# KW_Control.net
KiCad netlist of a schematic drawn in EAGLE
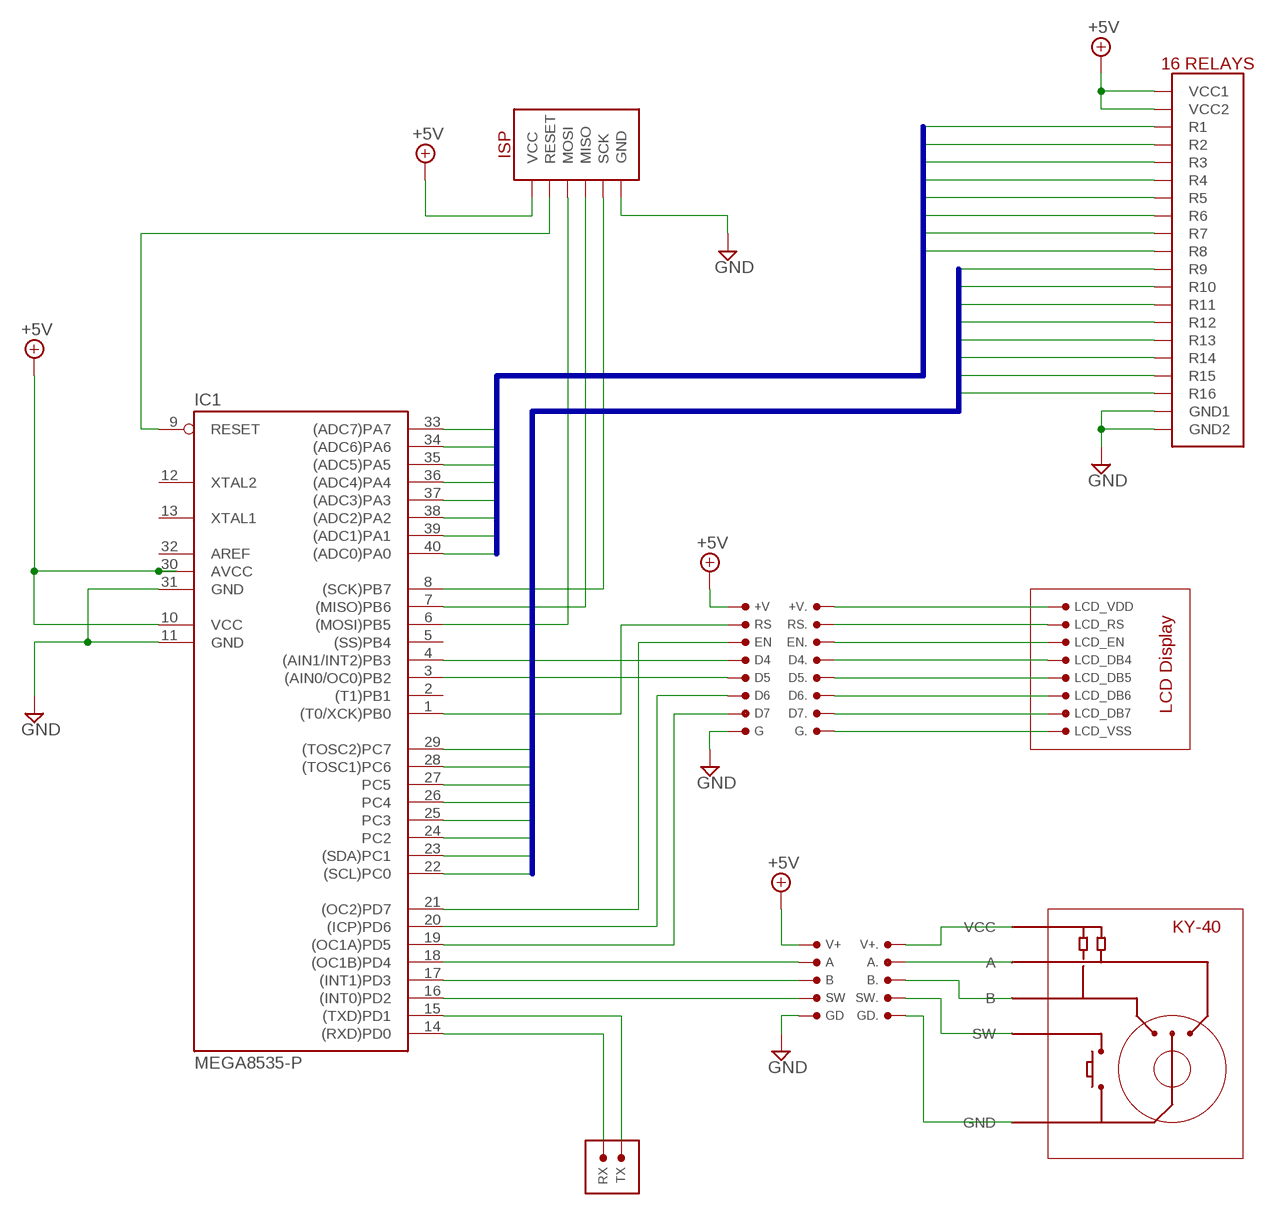
[diagram p0: schematic, sheet 1]

(export (version "E")
  (design (tool "Eeschema 10.0.6"))
  (components
    (comp (ref "+V")
      (value "PIN")
      (footprint "eagle-import:PIN")
      (libsource (lib "eagle-import") (part "PIN"))
    )
    (comp (ref "+V.")
      (value "PIN")
      (footprint "eagle-import:PIN")
      (libsource (lib "eagle-import") (part "PIN"))
    )
    (comp (ref "A")
      (value "PIN")
      (footprint "eagle-import:PIN")
      (libsource (lib "eagle-import") (part "PIN"))
    )
    (comp (ref "A.")
      (value "PIN")
      (footprint "eagle-import:PIN")
      (libsource (lib "eagle-import") (part "PIN"))
    )
    (comp (ref "B")
      (value "PIN")
      (footprint "eagle-import:PIN")
      (libsource (lib "eagle-import") (part "PIN"))
    )
    (comp (ref "B.")
      (value "PIN")
      (footprint "eagle-import:PIN")
      (libsource (lib "eagle-import") (part "PIN"))
    )
    (comp (ref "D4")
      (value "PIN")
      (footprint "eagle-import:PIN")
      (libsource (lib "eagle-import") (part "PIN"))
    )
    (comp (ref "D4.")
      (value "PIN")
      (footprint "eagle-import:PIN")
      (libsource (lib "eagle-import") (part "PIN"))
    )
    (comp (ref "D5")
      (value "PIN")
      (footprint "eagle-import:PIN")
      (libsource (lib "eagle-import") (part "PIN"))
    )
    (comp (ref "D5.")
      (value "PIN")
      (footprint "eagle-import:PIN")
      (libsource (lib "eagle-import") (part "PIN"))
    )
    (comp (ref "D6")
      (value "PIN")
      (footprint "eagle-import:PIN")
      (libsource (lib "eagle-import") (part "PIN"))
    )
    (comp (ref "D6.")
      (value "PIN")
      (footprint "eagle-import:PIN")
      (libsource (lib "eagle-import") (part "PIN"))
    )
    (comp (ref "D7")
      (value "PIN")
      (footprint "eagle-import:PIN")
      (libsource (lib "eagle-import") (part "PIN"))
    )
    (comp (ref "D7.")
      (value "PIN")
      (footprint "eagle-import:PIN")
      (libsource (lib "eagle-import") (part "PIN"))
    )
    (comp (ref "EN")
      (value "PIN")
      (footprint "eagle-import:PIN")
      (libsource (lib "eagle-import") (part "PIN"))
    )
    (comp (ref "EN.")
      (value "PIN")
      (footprint "eagle-import:PIN")
      (libsource (lib "eagle-import") (part "PIN"))
    )
    (comp (ref "G")
      (value "PIN")
      (footprint "eagle-import:PIN")
      (libsource (lib "eagle-import") (part "PIN"))
    )
    (comp (ref "G.")
      (value "PIN")
      (footprint "eagle-import:PIN")
      (libsource (lib "eagle-import") (part "PIN"))
    )
    (comp (ref "GD")
      (value "PIN")
      (footprint "eagle-import:PIN")
      (libsource (lib "eagle-import") (part "PIN"))
    )
    (comp (ref "GD.")
      (value "PIN")
      (footprint "eagle-import:PIN")
      (libsource (lib "eagle-import") (part "PIN"))
    )
    (comp (ref "IC1")
      (value "MEGA8535-P")
      (footprint "eagle-import:DIL40")
      (fields (field (name "MPN") "ATMEGA8535-16PU"))
      (libsource (lib "eagle-import") (part "MEGA8535-P"))
    )
    (comp (ref "IC2")
      (value "KY-40")
      (footprint "eagle-import:KY-40")
      (libsource (lib "eagle-import") (part "KY-40"))
    )
    (comp (ref "LCD_DB4")
      (value "PIN")
      (footprint "eagle-import:PIN")
      (libsource (lib "eagle-import") (part "PIN"))
    )
    (comp (ref "LCD_DB5")
      (value "PIN")
      (footprint "eagle-import:PIN")
      (libsource (lib "eagle-import") (part "PIN"))
    )
    (comp (ref "LCD_DB6")
      (value "PIN")
      (footprint "eagle-import:PIN")
      (libsource (lib "eagle-import") (part "PIN"))
    )
    (comp (ref "LCD_DB7")
      (value "PIN")
      (footprint "eagle-import:PIN")
      (libsource (lib "eagle-import") (part "PIN"))
    )
    (comp (ref "LCD_EN")
      (value "PIN")
      (footprint "eagle-import:PIN")
      (libsource (lib "eagle-import") (part "PIN"))
    )
    (comp (ref "LCD_RS")
      (value "PIN")
      (footprint "eagle-import:PIN")
      (libsource (lib "eagle-import") (part "PIN"))
    )
    (comp (ref "LCD_VDD")
      (value "PIN")
      (footprint "eagle-import:PIN")
      (libsource (lib "eagle-import") (part "PIN"))
    )
    (comp (ref "LCD_VSS")
      (value "PIN")
      (footprint "eagle-import:PIN")
      (libsource (lib "eagle-import") (part "PIN"))
    )
    (comp (ref "RS")
      (value "PIN")
      (footprint "eagle-import:PIN")
      (libsource (lib "eagle-import") (part "PIN"))
    )
    (comp (ref "RS.")
      (value "PIN")
      (footprint "eagle-import:PIN")
      (libsource (lib "eagle-import") (part "PIN"))
    )
    (comp (ref "RX")
      (value "PIN")
      (footprint "eagle-import:PIN")
      (libsource (lib "eagle-import") (part "PIN"))
    )
    (comp (ref "SW")
      (value "PIN")
      (footprint "eagle-import:PIN")
      (libsource (lib "eagle-import") (part "PIN"))
    )
    (comp (ref "SW.")
      (value "PIN")
      (footprint "eagle-import:PIN")
      (libsource (lib "eagle-import") (part "PIN"))
    )
    (comp (ref "TX")
      (value "PIN")
      (footprint "eagle-import:PIN")
      (libsource (lib "eagle-import") (part "PIN"))
    )
    (comp (ref "U$1")
      (value "ISP")
      (footprint "eagle-import:ISP")
      (libsource (lib "eagle-import") (part "ISP"))
    )
    (comp (ref "U$2")
      (value "RELAYS-16")
      (footprint "eagle-import:RELAYS-16")
      (libsource (lib "eagle-import") (part "RELAYS-16"))
    )
    (comp (ref "V+")
      (value "PIN")
      (footprint "eagle-import:PIN")
      (libsource (lib "eagle-import") (part "PIN"))
    )
    (comp (ref "V+.")
      (value "PIN")
      (footprint "eagle-import:PIN")
      (libsource (lib "eagle-import") (part "PIN"))
    )
  )
  (nets
    (net (code "1") (name "+5V") (class "Default")
      (node (ref "+V") (pin "P$1") (pinfunction "PIN1_P$1") (pintype "bidirectional"))
      (node (ref "IC1") (pin "10") (pinfunction "VCC_10") (pintype "power_in"))
      (node (ref "IC1") (pin "30") (pinfunction "AVCC_30") (pintype "power_in"))
      (node (ref "U$1") (pin "VCC") (pinfunction "VCC_VCC") (pintype "power_in"))
      (node (ref "U$2") (pin "VCC1") (pinfunction "VCC1_VCC1") (pintype "power_in"))
      (node (ref "U$2") (pin "VCC2") (pinfunction "VCC2_VCC2") (pintype "power_in"))
      (node (ref "V+") (pin "P$1") (pinfunction "PIN1_P$1") (pintype "bidirectional"))
    )
    (net (code "2") (name "/A1") (class "Default")
      (node (ref "IC1") (pin "40") (pinfunction "(ADC0)PA0_40") (pintype "bidirectional"))
      (node (ref "U$2") (pin "1") (pinfunction "R1_1") (pintype "input"))
    )
    (net (code "3") (name "/A2") (class "Default")
      (node (ref "IC1") (pin "39") (pinfunction "(ADC1)PA1_39") (pintype "bidirectional"))
      (node (ref "U$2") (pin "2") (pinfunction "R2_2") (pintype "input"))
    )
    (net (code "4") (name "/A3") (class "Default")
      (node (ref "IC1") (pin "38") (pinfunction "(ADC2)PA2_38") (pintype "bidirectional"))
      (node (ref "U$2") (pin "3") (pinfunction "R3_3") (pintype "input"))
    )
    (net (code "5") (name "/A4") (class "Default")
      (node (ref "IC1") (pin "37") (pinfunction "(ADC3)PA3_37") (pintype "bidirectional"))
      (node (ref "U$2") (pin "4") (pinfunction "R4_4") (pintype "input"))
    )
    (net (code "6") (name "/A5") (class "Default")
      (node (ref "IC1") (pin "36") (pinfunction "(ADC4)PA4_36") (pintype "bidirectional"))
      (node (ref "U$2") (pin "5") (pinfunction "R5_5") (pintype "input"))
    )
    (net (code "7") (name "/A6") (class "Default")
      (node (ref "IC1") (pin "35") (pinfunction "(ADC5)PA5_35") (pintype "bidirectional"))
      (node (ref "U$2") (pin "6") (pinfunction "R6_6") (pintype "input"))
    )
    (net (code "8") (name "/A7") (class "Default")
      (node (ref "IC1") (pin "34") (pinfunction "(ADC6)PA6_34") (pintype "bidirectional"))
      (node (ref "U$2") (pin "7") (pinfunction "R7_7") (pintype "input"))
    )
    (net (code "9") (name "/A8") (class "Default")
      (node (ref "IC1") (pin "33") (pinfunction "(ADC7)PA7_33") (pintype "bidirectional"))
      (node (ref "U$2") (pin "8") (pinfunction "R8_8") (pintype "input"))
    )
    (net (code "10") (name "/B1") (class "Default")
      (node (ref "IC1") (pin "22") (pinfunction "(SCL)PC0_22") (pintype "bidirectional"))
      (node (ref "U$2") (pin "9") (pinfunction "R9_9") (pintype "input"))
    )
    (net (code "11") (name "/B2") (class "Default")
      (node (ref "IC1") (pin "23") (pinfunction "(SDA)PC1_23") (pintype "bidirectional"))
      (node (ref "U$2") (pin "10") (pinfunction "R10_10") (pintype "input"))
    )
    (net (code "12") (name "/B3") (class "Default")
      (node (ref "IC1") (pin "24") (pinfunction "PC2_24") (pintype "bidirectional"))
      (node (ref "U$2") (pin "11") (pinfunction "R11_11") (pintype "input"))
    )
    (net (code "13") (name "/B4") (class "Default")
      (node (ref "IC1") (pin "25") (pinfunction "PC3_25") (pintype "bidirectional"))
      (node (ref "U$2") (pin "12") (pinfunction "R12_12") (pintype "input"))
    )
    (net (code "14") (name "/B5") (class "Default")
      (node (ref "IC1") (pin "26") (pinfunction "PC4_26") (pintype "bidirectional"))
      (node (ref "U$2") (pin "13") (pinfunction "R13_13") (pintype "input"))
    )
    (net (code "15") (name "/B6") (class "Default")
      (node (ref "IC1") (pin "27") (pinfunction "PC5_27") (pintype "bidirectional"))
      (node (ref "U$2") (pin "14") (pinfunction "R14_14") (pintype "input"))
    )
    (net (code "16") (name "/B7") (class "Default")
      (node (ref "IC1") (pin "28") (pinfunction "(TOSC1)PC6_28") (pintype "bidirectional"))
      (node (ref "U$2") (pin "15") (pinfunction "R15_15") (pintype "input"))
    )
    (net (code "17") (name "/B8") (class "Default")
      (node (ref "IC1") (pin "29") (pinfunction "(TOSC2)PC7_29") (pintype "bidirectional"))
      (node (ref "U$2") (pin "16") (pinfunction "R16_16") (pintype "input"))
    )
    (net (code "18") (name "GND") (class "Default")
      (node (ref "G") (pin "P$1") (pinfunction "PIN1_P$1") (pintype "bidirectional"))
      (node (ref "GD") (pin "P$1") (pinfunction "PIN1_P$1") (pintype "bidirectional"))
      (node (ref "IC1") (pin "11") (pinfunction "GND_11") (pintype "power_in"))
      (node (ref "IC1") (pin "31") (pinfunction "GND_31") (pintype "power_in"))
      (node (ref "U$1") (pin "GND") (pinfunction "GND_GND") (pintype "power_in"))
      (node (ref "U$2") (pin "GND1") (pinfunction "GND1_GND1") (pintype "power_in"))
      (node (ref "U$2") (pin "GND2") (pinfunction "GND2_GND2") (pintype "power_in"))
    )
    (net (code "19") (name "Net-(+V.-PIN1)") (class "Default")
      (node (ref "+V.") (pin "P$1") (pinfunction "PIN1_P$1") (pintype "bidirectional"))
      (node (ref "LCD_VDD") (pin "P$1") (pinfunction "PIN1_P$1") (pintype "bidirectional"))
    )
    (net (code "20") (name "Net-(A-PIN1)") (class "Default")
      (node (ref "A") (pin "P$1") (pinfunction "PIN1_P$1") (pintype "bidirectional"))
      (node (ref "IC1") (pin "18") (pinfunction "(OC1B)PD4_18") (pintype "bidirectional"))
    )
    (net (code "21") (name "Net-(A.-PIN1)") (class "Default")
      (node (ref "A.") (pin "P$1") (pinfunction "PIN1_P$1") (pintype "bidirectional"))
      (node (ref "IC2") (pin "A") (pinfunction "A_A") (pintype "output"))
    )
    (net (code "22") (name "Net-(B-PIN1)") (class "Default")
      (node (ref "B") (pin "P$1") (pinfunction "PIN1_P$1") (pintype "bidirectional"))
      (node (ref "IC1") (pin "17") (pinfunction "(INT1)PD3_17") (pintype "bidirectional"))
    )
    (net (code "23") (name "Net-(B.-PIN1)") (class "Default")
      (node (ref "B.") (pin "P$1") (pinfunction "PIN1_P$1") (pintype "bidirectional"))
      (node (ref "IC2") (pin "B") (pinfunction "B_B") (pintype "output"))
    )
    (net (code "24") (name "Net-(D4-PIN1)") (class "Default")
      (node (ref "D4") (pin "P$1") (pinfunction "PIN1_P$1") (pintype "bidirectional"))
      (node (ref "IC1") (pin "4") (pinfunction "(AIN1/INT2)PB3_4") (pintype "bidirectional"))
    )
    (net (code "25") (name "Net-(D4.-PIN1)") (class "Default")
      (node (ref "D4.") (pin "P$1") (pinfunction "PIN1_P$1") (pintype "bidirectional"))
      (node (ref "LCD_DB4") (pin "P$1") (pinfunction "PIN1_P$1") (pintype "bidirectional"))
    )
    (net (code "26") (name "Net-(D5-PIN1)") (class "Default")
      (node (ref "D5") (pin "P$1") (pinfunction "PIN1_P$1") (pintype "bidirectional"))
      (node (ref "IC1") (pin "3") (pinfunction "(AIN0/OC0)PB2_3") (pintype "bidirectional"))
    )
    (net (code "27") (name "Net-(D5.-PIN1)") (class "Default")
      (node (ref "D5.") (pin "P$1") (pinfunction "PIN1_P$1") (pintype "bidirectional"))
      (node (ref "LCD_DB5") (pin "P$1") (pinfunction "PIN1_P$1") (pintype "bidirectional"))
    )
    (net (code "28") (name "Net-(D6-PIN1)") (class "Default")
      (node (ref "D6") (pin "P$1") (pinfunction "PIN1_P$1") (pintype "bidirectional"))
      (node (ref "IC1") (pin "20") (pinfunction "(ICP)PD6_20") (pintype "bidirectional"))
    )
    (net (code "29") (name "Net-(D6.-PIN1)") (class "Default")
      (node (ref "D6.") (pin "P$1") (pinfunction "PIN1_P$1") (pintype "bidirectional"))
      (node (ref "LCD_DB6") (pin "P$1") (pinfunction "PIN1_P$1") (pintype "bidirectional"))
    )
    (net (code "30") (name "Net-(D7-PIN1)") (class "Default")
      (node (ref "D7") (pin "P$1") (pinfunction "PIN1_P$1") (pintype "bidirectional"))
      (node (ref "IC1") (pin "19") (pinfunction "(OC1A)PD5_19") (pintype "bidirectional"))
    )
    (net (code "31") (name "Net-(D7.-PIN1)") (class "Default")
      (node (ref "D7.") (pin "P$1") (pinfunction "PIN1_P$1") (pintype "bidirectional"))
      (node (ref "LCD_DB7") (pin "P$1") (pinfunction "PIN1_P$1") (pintype "bidirectional"))
    )
    (net (code "32") (name "Net-(EN-PIN1)") (class "Default")
      (node (ref "EN") (pin "P$1") (pinfunction "PIN1_P$1") (pintype "bidirectional"))
      (node (ref "IC1") (pin "21") (pinfunction "(OC2)PD7_21") (pintype "bidirectional"))
    )
    (net (code "33") (name "Net-(EN.-PIN1)") (class "Default")
      (node (ref "EN.") (pin "P$1") (pinfunction "PIN1_P$1") (pintype "bidirectional"))
      (node (ref "LCD_EN") (pin "P$1") (pinfunction "PIN1_P$1") (pintype "bidirectional"))
    )
    (net (code "34") (name "Net-(G.-PIN1)") (class "Default")
      (node (ref "G.") (pin "P$1") (pinfunction "PIN1_P$1") (pintype "bidirectional"))
      (node (ref "LCD_VSS") (pin "P$1") (pinfunction "PIN1_P$1") (pintype "bidirectional"))
    )
    (net (code "35") (name "Net-(GD.-PIN1)") (class "Default")
      (node (ref "GD.") (pin "P$1") (pinfunction "PIN1_P$1") (pintype "bidirectional"))
      (node (ref "IC2") (pin "GND") (pinfunction "GND_GND") (pintype "power_in"))
    )
    (net (code "36") (name "Net-(IC1-(INT0)PD2)") (class "Default")
      (node (ref "IC1") (pin "16") (pinfunction "(INT0)PD2_16") (pintype "bidirectional"))
      (node (ref "SW") (pin "P$1") (pinfunction "PIN1_P$1") (pintype "bidirectional"))
    )
    (net (code "37") (name "Net-(IC1-(MISO)PB6)") (class "Default")
      (node (ref "IC1") (pin "7") (pinfunction "(MISO)PB6_7") (pintype "bidirectional"))
      (node (ref "U$1") (pin "MISO") (pinfunction "MISO_MISO") (pintype "input"))
    )
    (net (code "38") (name "Net-(IC1-(MOSI)PB5)") (class "Default")
      (node (ref "IC1") (pin "6") (pinfunction "(MOSI)PB5_6") (pintype "bidirectional"))
      (node (ref "U$1") (pin "MOSI") (pinfunction "MOSI_MOSI") (pintype "output"))
    )
    (net (code "39") (name "Net-(IC1-(RXD)PD0)") (class "Default")
      (node (ref "IC1") (pin "14") (pinfunction "(RXD)PD0_14") (pintype "bidirectional"))
      (node (ref "RX") (pin "P$1") (pinfunction "PIN1_P$1") (pintype "bidirectional"))
    )
    (net (code "40") (name "Net-(IC1-(SCK)PB7)") (class "Default")
      (node (ref "IC1") (pin "8") (pinfunction "(SCK)PB7_8") (pintype "bidirectional"))
      (node (ref "U$1") (pin "SCK") (pinfunction "SCK_SCK") (pintype "output"))
    )
    (net (code "41") (name "Net-(IC1-(T0{slash}XCK)PB0)") (class "Default")
      (node (ref "IC1") (pin "1") (pinfunction "(T0/XCK)PB0_1") (pintype "bidirectional"))
      (node (ref "RS") (pin "P$1") (pinfunction "PIN1_P$1") (pintype "bidirectional"))
    )
    (net (code "42") (name "Net-(IC1-(TXD)PD1)") (class "Default")
      (node (ref "IC1") (pin "15") (pinfunction "(TXD)PD1_15") (pintype "bidirectional"))
      (node (ref "TX") (pin "P$1") (pinfunction "PIN1_P$1") (pintype "bidirectional"))
    )
    (net (code "43") (name "Net-(IC1-RESET)") (class "Default")
      (node (ref "IC1") (pin "9") (pinfunction "RESET_9") (pintype "input"))
      (node (ref "U$1") (pin "RESET") (pinfunction "RESET_RESET") (pintype "output"))
    )
    (net (code "44") (name "Net-(LCD_RS-PIN1)") (class "Default")
      (node (ref "LCD_RS") (pin "P$1") (pinfunction "PIN1_P$1") (pintype "bidirectional"))
      (node (ref "RS.") (pin "P$1") (pinfunction "PIN1_P$1") (pintype "bidirectional"))
    )
    (net (code "45") (name "Net-(SW.-PIN1)") (class "Default")
      (node (ref "IC2") (pin "SW") (pinfunction "SW_SW") (pintype "output"))
      (node (ref "SW.") (pin "P$1") (pinfunction "PIN1_P$1") (pintype "bidirectional"))
    )
    (net (code "46") (name "Net-(V+.-PIN1)") (class "Default")
      (node (ref "IC2") (pin "VCC") (pinfunction "VCC_VCC") (pintype "power_in"))
      (node (ref "V+.") (pin "P$1") (pinfunction "PIN1_P$1") (pintype "bidirectional"))
    )
    (net (code "47") (name "unconnected-(IC1-(SS)PB4-Pad5)") (class "Default")
      (node (ref "IC1") (pin "5") (pinfunction "(SS)PB4_5") (pintype "bidirectional"))
    )
    (net (code "48") (name "unconnected-(IC1-(T1)PB1-Pad2)") (class "Default")
      (node (ref "IC1") (pin "2") (pinfunction "(T1)PB1_2") (pintype "bidirectional"))
    )
    (net (code "49") (name "unconnected-(IC1-AREF-Pad32)") (class "Default")
      (node (ref "IC1") (pin "32") (pinfunction "AREF_32") (pintype "passive"))
    )
    (net (code "50") (name "unconnected-(IC1-XTAL1-Pad13)") (class "Default")
      (node (ref "IC1") (pin "13") (pinfunction "XTAL1_13") (pintype "bidirectional"))
    )
    (net (code "51") (name "unconnected-(IC1-XTAL2-Pad12)") (class "Default")
      (node (ref "IC1") (pin "12") (pinfunction "XTAL2_12") (pintype "bidirectional"))
    )
  )
)
